# EMS_esp32_wifi_lora_gsm_v2_7_2.net
KiCad netlist of a schematic drawn in EAGLE
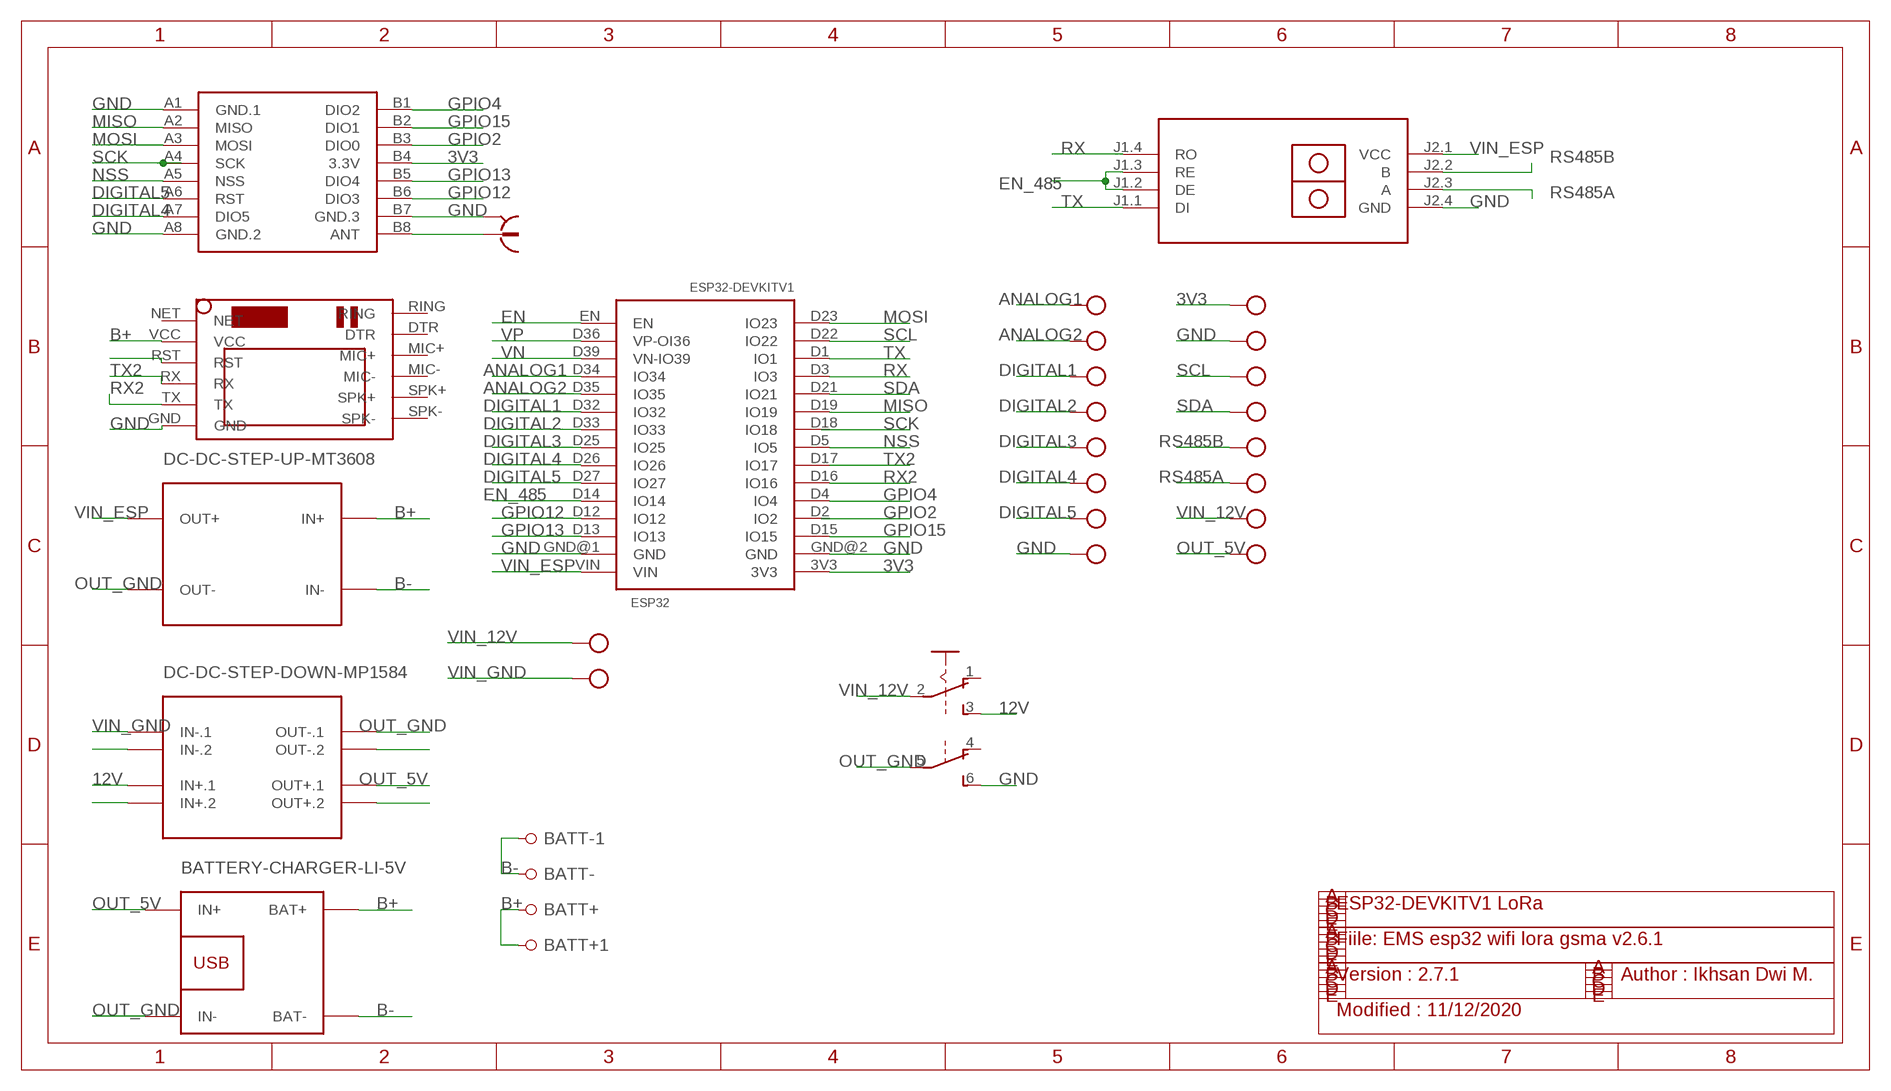
[diagram p0: schematic, sheet 1]

(export (version "E")
  (design (tool "Eeschema 10.0.6"))
  (components
    (comp (ref "3V3__GND")
      (value "MKDSN1,5/2-5,08")
      (footprint "eagle-import:MKDSN1,5_2-5,08")
      (libsource (lib "eagle-import") (part "MKDSN1,5/2-5,08"))
    )
    (comp (ref "12V__5V")
      (value "MKDSN1,5/2-5,08")
      (footprint "eagle-import:MKDSN1,5_2-5,08")
      (libsource (lib "eagle-import") (part "MKDSN1,5/2-5,08"))
    )
    (comp (ref "A1__A2")
      (value "MKDSN1,5/2-5,08")
      (footprint "eagle-import:MKDSN1,5_2-5,08")
      (libsource (lib "eagle-import") (part "MKDSN1,5/2-5,08"))
    )
    (comp (ref "A_____B")
      (value "MKDSN1,5/2-5,08")
      (footprint "eagle-import:MKDSN1,5_2-5,08")
      (libsource (lib "eagle-import") (part "MKDSN1,5/2-5,08"))
    )
    (comp (ref "BATT+")
      (value "PIN-1X1_2.00")
      (footprint "eagle-import:1X01M")
      (libsource (lib "eagle-import") (part "PIN-1X1_2.00"))
    )
    (comp (ref "BATT+1")
      (value "PIN-1X1_2.00")
      (footprint "eagle-import:1X01M")
      (libsource (lib "eagle-import") (part "PIN-1X1_2.00"))
    )
    (comp (ref "BATT-")
      (value "PIN-1X1")
      (footprint "eagle-import:1X01NONAME")
      (libsource (lib "eagle-import") (part "PIN-1X1"))
    )
    (comp (ref "BATT-1")
      (value "PIN-1X1")
      (footprint "eagle-import:1X01NONAME")
      (libsource (lib "eagle-import") (part "PIN-1X1"))
    )
    (comp (ref "D1__D2")
      (value "MKDSN1,5/2-5,08")
      (footprint "eagle-import:MKDSN1,5_2-5,08")
      (libsource (lib "eagle-import") (part "MKDSN1,5/2-5,08"))
    )
    (comp (ref "D3__D4")
      (value "MKDSN1,5/2-5,08")
      (footprint "eagle-import:MKDSN1,5_2-5,08")
      (libsource (lib "eagle-import") (part "MKDSN1,5/2-5,08"))
    )
    (comp (ref "D5_GND")
      (value "MKDSN1,5/2-5,08")
      (footprint "eagle-import:MKDSN1,5_2-5,08")
      (libsource (lib "eagle-import") (part "MKDSN1,5/2-5,08"))
    )
    (comp (ref "ESP32")
      (value "ESP32DEVKITV1")
      (footprint "eagle-import:ESP32-DEVKITV1")
      (libsource (lib "eagle-import") (part "ESP32DEVKITV1"))
    )
    (comp (ref "S1")
      (value "A68-A31")
      (footprint "eagle-import:A68-A31")
      (libsource (lib "eagle-import") (part "A68-A31"))
    )
    (comp (ref "SCL__SDA")
      (value "MKDSN1,5/2-5,08")
      (footprint "eagle-import:MKDSN1,5_2-5,08")
      (libsource (lib "eagle-import") (part "MKDSN1,5/2-5,08"))
    )
    (comp (ref "U$1")
      (value "RS485-TTL-CONVERTER")
      (footprint "eagle-import:RS485-TTL-CONVERTER")
      (libsource (lib "eagle-import") (part "RS485-TTL-CONVERTER"))
    )
    (comp (ref "U$2")
      (value "DC-DC-STEP-UP-MT3608")
      (footprint "eagle-import:DC-DC-STEP-UP-MT3608")
      (libsource (lib "eagle-import") (part "DC-DC-STEP-UP-MT3608"))
    )
    (comp (ref "U$3")
      (value "DC-DC-STEP-DOWN-MP1584")
      (footprint "eagle-import:DC-DC-STEP-DOWN-MP1584")
      (libsource (lib "eagle-import") (part "DC-DC-STEP-DOWN-MP1584"))
    )
    (comp (ref "U$4")
      (value "BATTERY-CHARGER-LI-5V")
      (footprint "eagle-import:BATTERY-CHARGER-LI-5V")
      (libsource (lib "eagle-import") (part "BATTERY-CHARGER-LI-5V"))
    )
    (comp (ref "U$5")
      (value "WIRELESS-LORA-RFM95W#SMD")
      (footprint "eagle-import:WIRELESS-LORA-RFM95W#SMD")
      (libsource (lib "eagle-import") (part "WIRELESS-LORA-RFM95W#SMD"))
    )
    (comp (ref "U$9")
      (value "SIM800LMODULE")
      (footprint "eagle-import:SIM800LMODULE")
      (libsource (lib "eagle-import") (part "SIM800LMODULE"))
    )
    (comp (ref "X1")
      (value "734120110")
      (footprint "eagle-import:734120110")
      (libsource (lib "eagle-import") (part "734120110"))
    )
    (comp (ref "X10")
      (value "MKDSN1,5/2-5,08")
      (footprint "eagle-import:MKDSN1,5_2-5,08")
      (libsource (lib "eagle-import") (part "MKDSN1,5/2-5,08"))
    )
  )
  (nets
    (net (code "1") (name "/3V3") (class "Default")
      (node (ref "3V3__GND") (pin "1") (pinfunction "KL_1") (pintype "passive"))
      (node (ref "ESP32") (pin "3V3") (pinfunction "3V3_3V3") (pintype "bidirectional"))
      (node (ref "U$5") (pin "B4") (pinfunction "3.3V_B4") (pintype "power_in"))
    )
    (net (code "2") (name "/12V") (class "Default")
      (node (ref "S1") (pin "3") (pinfunction "S_3") (pintype "passive"))
      (node (ref "U$3") (pin "IN+.1") (pinfunction "IN+.1_IN+.1") (pintype "bidirectional"))
    )
    (net (code "3") (name "/ANALOG1") (class "Default")
      (node (ref "A1__A2") (pin "1") (pinfunction "KL_1") (pintype "passive"))
      (node (ref "ESP32") (pin "D34") (pinfunction "IO34_D34") (pintype "bidirectional"))
    )
    (net (code "4") (name "/ANALOG2") (class "Default")
      (node (ref "A1__A2") (pin "2") (pinfunction "KL_2") (pintype "passive"))
      (node (ref "ESP32") (pin "D35") (pinfunction "IO35_D35") (pintype "bidirectional"))
    )
    (net (code "5") (name "/B+") (class "Default")
      (node (ref "BATT+") (pin "1") (pinfunction "1_1") (pintype "passive"))
      (node (ref "BATT+1") (pin "1") (pinfunction "1_1") (pintype "passive"))
      (node (ref "U$2") (pin "IN+") (pinfunction "IN+_IN+") (pintype "bidirectional"))
      (node (ref "U$4") (pin "BAT+") (pinfunction "BAT+_BAT+") (pintype "bidirectional"))
      (node (ref "U$9") (pin "VCC") (pinfunction "VCC_VCC") (pintype "bidirectional"))
    )
    (net (code "6") (name "/B-") (class "Default")
      (node (ref "BATT-") (pin "1") (pinfunction "1_1") (pintype "passive"))
      (node (ref "BATT-1") (pin "1") (pinfunction "1_1") (pintype "passive"))
      (node (ref "U$2") (pin "IN-") (pinfunction "IN-_IN-") (pintype "bidirectional"))
      (node (ref "U$4") (pin "BAT-") (pinfunction "BAT-_BAT-") (pintype "bidirectional"))
    )
    (net (code "7") (name "/DIGITAL1") (class "Default")
      (node (ref "D1__D2") (pin "1") (pinfunction "KL_1") (pintype "passive"))
      (node (ref "ESP32") (pin "D32") (pinfunction "IO32_D32") (pintype "bidirectional"))
    )
    (net (code "8") (name "/DIGITAL2") (class "Default")
      (node (ref "D1__D2") (pin "2") (pinfunction "KL_2") (pintype "passive"))
      (node (ref "ESP32") (pin "D33") (pinfunction "IO33_D33") (pintype "bidirectional"))
    )
    (net (code "9") (name "/DIGITAL3") (class "Default")
      (node (ref "D3__D4") (pin "1") (pinfunction "KL_1") (pintype "passive"))
      (node (ref "ESP32") (pin "D25") (pinfunction "IO25_D25") (pintype "bidirectional"))
    )
    (net (code "10") (name "/DIGITAL4") (class "Default")
      (node (ref "D3__D4") (pin "2") (pinfunction "KL_2") (pintype "passive"))
      (node (ref "ESP32") (pin "D26") (pinfunction "IO26_D26") (pintype "bidirectional"))
      (node (ref "U$5") (pin "A7") (pinfunction "DIO5_A7") (pintype "bidirectional"))
    )
    (net (code "11") (name "/DIGITAL5") (class "Default")
      (node (ref "D5_GND") (pin "1") (pinfunction "KL_1") (pintype "passive"))
      (node (ref "ESP32") (pin "D27") (pinfunction "IO27_D27") (pintype "bidirectional"))
      (node (ref "U$5") (pin "A6") (pinfunction "RST_A6") (pintype "bidirectional"))
    )
    (net (code "12") (name "/EN") (class "Default")
      (node (ref "ESP32") (pin "EN") (pinfunction "EN_EN") (pintype "bidirectional"))
    )
    (net (code "13") (name "/EN_485") (class "Default")
      (node (ref "ESP32") (pin "D14") (pinfunction "IO14_D14") (pintype "bidirectional"))
      (node (ref "U$1") (pin "J1.2") (pinfunction "DE_J1.2") (pintype "passive"))
      (node (ref "U$1") (pin "J1.3") (pinfunction "RE_J1.3") (pintype "passive"))
    )
    (net (code "14") (name "/GND") (class "Default")
      (node (ref "3V3__GND") (pin "2") (pinfunction "KL_2") (pintype "passive"))
      (node (ref "D5_GND") (pin "2") (pinfunction "KL_2") (pintype "passive"))
      (node (ref "ESP32") (pin "GND@1") (pinfunction "GND_GND@1") (pintype "bidirectional"))
      (node (ref "ESP32") (pin "GND@2") (pinfunction "GND_GND@2") (pintype "bidirectional"))
      (node (ref "S1") (pin "6") (pinfunction "S_6") (pintype "passive"))
      (node (ref "U$1") (pin "J2.4") (pinfunction "GND_J2.4") (pintype "power_in"))
      (node (ref "U$5") (pin "A1") (pinfunction "GND.1_A1") (pintype "power_in"))
      (node (ref "U$5") (pin "A8") (pinfunction "GND.2_A8") (pintype "power_in"))
      (node (ref "U$5") (pin "B7") (pinfunction "GND.3_B7") (pintype "power_in"))
      (node (ref "U$9") (pin "GND") (pinfunction "GND_GND") (pintype "bidirectional"))
      (node (ref "X1") (pin "S@1") (pinfunction "2_S@1") (pintype "passive"))
      (node (ref "X1") (pin "S@2") (pinfunction "2_S@2") (pintype "passive"))
      (node (ref "X1") (pin "S@3") (pinfunction "2_S@3") (pintype "passive"))
    )
    (net (code "15") (name "/GPIO2") (class "Default")
      (node (ref "ESP32") (pin "D2") (pinfunction "IO2_D2") (pintype "bidirectional"))
      (node (ref "U$5") (pin "B3") (pinfunction "DIO0_B3") (pintype "bidirectional"))
    )
    (net (code "16") (name "/GPIO4") (class "Default")
      (node (ref "ESP32") (pin "D4") (pinfunction "IO4_D4") (pintype "bidirectional"))
      (node (ref "U$5") (pin "B1") (pinfunction "DIO2_B1") (pintype "bidirectional"))
    )
    (net (code "17") (name "/GPIO12") (class "Default")
      (node (ref "ESP32") (pin "D12") (pinfunction "IO12_D12") (pintype "bidirectional"))
      (node (ref "U$5") (pin "B6") (pinfunction "DIO3_B6") (pintype "bidirectional"))
    )
    (net (code "18") (name "/GPIO13") (class "Default")
      (node (ref "ESP32") (pin "D13") (pinfunction "IO13_D13") (pintype "bidirectional"))
      (node (ref "U$5") (pin "B5") (pinfunction "DIO4_B5") (pintype "bidirectional"))
    )
    (net (code "19") (name "/GPIO15") (class "Default")
      (node (ref "ESP32") (pin "D15") (pinfunction "IO15_D15") (pintype "bidirectional"))
      (node (ref "U$5") (pin "B2") (pinfunction "DIO1_B2") (pintype "bidirectional"))
    )
    (net (code "20") (name "/MISO") (class "Default")
      (node (ref "ESP32") (pin "D19") (pinfunction "IO19_D19") (pintype "bidirectional"))
      (node (ref "U$5") (pin "A2") (pinfunction "MISO_A2") (pintype "bidirectional"))
    )
    (net (code "21") (name "/MOSI") (class "Default")
      (node (ref "ESP32") (pin "D23") (pinfunction "IO23_D23") (pintype "bidirectional"))
      (node (ref "U$5") (pin "A3") (pinfunction "MOSI_A3") (pintype "bidirectional"))
    )
    (net (code "22") (name "/NSS") (class "Default")
      (node (ref "ESP32") (pin "D5") (pinfunction "IO5_D5") (pintype "bidirectional"))
      (node (ref "U$5") (pin "A5") (pinfunction "NSS_A5") (pintype "bidirectional"))
    )
    (net (code "23") (name "/OUT_5V") (class "Default")
      (node (ref "12V__5V") (pin "2") (pinfunction "KL_2") (pintype "passive"))
      (node (ref "U$3") (pin "OUT+.1") (pinfunction "OUT+.1_OUT+.1") (pintype "bidirectional"))
      (node (ref "U$4") (pin "IN+") (pinfunction "IN+_IN+") (pintype "bidirectional"))
    )
    (net (code "24") (name "/OUT_GND") (class "Default")
      (node (ref "S1") (pin "5") (pinfunction "P_5") (pintype "passive"))
      (node (ref "U$2") (pin "OUT-") (pinfunction "OUT-_OUT-") (pintype "bidirectional"))
      (node (ref "U$3") (pin "OUT-.1") (pinfunction "OUT-.1_OUT-.1") (pintype "bidirectional"))
      (node (ref "U$4") (pin "IN-") (pinfunction "IN-_IN-") (pintype "bidirectional"))
    )
    (net (code "25") (name "/RS485A") (class "Default")
      (node (ref "A_____B") (pin "2") (pinfunction "KL_2") (pintype "passive"))
      (node (ref "U$1") (pin "J2.3") (pinfunction "A_J2.3") (pintype "passive"))
    )
    (net (code "26") (name "/RS485B") (class "Default")
      (node (ref "A_____B") (pin "1") (pinfunction "KL_1") (pintype "passive"))
      (node (ref "U$1") (pin "J2.2") (pinfunction "B_J2.2") (pintype "passive"))
    )
    (net (code "27") (name "/RX") (class "Default")
      (node (ref "ESP32") (pin "D3") (pinfunction "IO3_D3") (pintype "bidirectional"))
      (node (ref "U$1") (pin "J1.4") (pinfunction "RO_J1.4") (pintype "passive"))
    )
    (net (code "28") (name "/RX2") (class "Default")
      (node (ref "ESP32") (pin "D16") (pinfunction "IO16_D16") (pintype "bidirectional"))
      (node (ref "U$9") (pin "TX") (pinfunction "TX_TX") (pintype "bidirectional"))
    )
    (net (code "29") (name "/SCK") (class "Default")
      (node (ref "ESP32") (pin "D18") (pinfunction "IO18_D18") (pintype "bidirectional"))
      (node (ref "U$5") (pin "A4") (pinfunction "SCK_A4") (pintype "bidirectional"))
    )
    (net (code "30") (name "/SCL") (class "Default")
      (node (ref "ESP32") (pin "D22") (pinfunction "IO22_D22") (pintype "bidirectional"))
      (node (ref "SCL__SDA") (pin "1") (pinfunction "KL_1") (pintype "passive"))
    )
    (net (code "31") (name "/SDA") (class "Default")
      (node (ref "ESP32") (pin "D21") (pinfunction "IO21_D21") (pintype "bidirectional"))
      (node (ref "SCL__SDA") (pin "2") (pinfunction "KL_2") (pintype "passive"))
    )
    (net (code "32") (name "/TX") (class "Default")
      (node (ref "ESP32") (pin "D1") (pinfunction "IO1_D1") (pintype "bidirectional"))
      (node (ref "U$1") (pin "J1.1") (pinfunction "DI_J1.1") (pintype "passive"))
    )
    (net (code "33") (name "/TX2") (class "Default")
      (node (ref "ESP32") (pin "D17") (pinfunction "IO17_D17") (pintype "bidirectional"))
      (node (ref "U$9") (pin "RX") (pinfunction "RX_RX") (pintype "bidirectional"))
    )
    (net (code "34") (name "/VIN_12V") (class "Default")
      (node (ref "12V__5V") (pin "1") (pinfunction "KL_1") (pintype "passive"))
      (node (ref "S1") (pin "2") (pinfunction "P_2") (pintype "passive"))
      (node (ref "X10") (pin "1") (pinfunction "KL_1") (pintype "passive"))
    )
    (net (code "35") (name "/VIN_ESP") (class "Default")
      (node (ref "ESP32") (pin "VIN") (pinfunction "VIN_VIN") (pintype "bidirectional"))
      (node (ref "U$1") (pin "J2.1") (pinfunction "VCC_J2.1") (pintype "power_in"))
      (node (ref "U$2") (pin "OUT+") (pinfunction "OUT+_OUT+") (pintype "bidirectional"))
    )
    (net (code "36") (name "/VIN_GND") (class "Default")
      (node (ref "U$3") (pin "IN-.1") (pinfunction "IN-.1_IN-.1") (pintype "bidirectional"))
      (node (ref "X10") (pin "2") (pinfunction "KL_2") (pintype "passive"))
    )
    (net (code "37") (name "/VN") (class "Default")
      (node (ref "ESP32") (pin "D39") (pinfunction "VN-IO39_D39") (pintype "bidirectional"))
    )
    (net (code "38") (name "/VP") (class "Default")
      (node (ref "ESP32") (pin "D36") (pinfunction "VP-OI36_D36") (pintype "bidirectional"))
    )
    (net (code "39") (name "Net-(U$5-ANT)") (class "Default")
      (node (ref "U$5") (pin "B8") (pinfunction "ANT_B8") (pintype "passive"))
      (node (ref "X1") (pin "1") (pinfunction "1_1") (pintype "passive"))
    )
    (net (code "40") (name "unconnected-(S1A-O-Pad1)") (class "Default")
      (node (ref "S1") (pin "1") (pinfunction "O_1") (pintype "passive"))
    )
    (net (code "41") (name "unconnected-(S1B-O-Pad4)") (class "Default")
      (node (ref "S1") (pin "4") (pinfunction "O_4") (pintype "passive"))
    )
    (net (code "42") (name "unconnected-(U$3-PadIN+.2)") (class "Default")
      (node (ref "U$3") (pin "IN+.2") (pinfunction "IN+.2_IN+.2") (pintype "bidirectional"))
    )
    (net (code "43") (name "unconnected-(U$3-PadIN-.2)") (class "Default")
      (node (ref "U$3") (pin "IN-.2") (pinfunction "IN-.2_IN-.2") (pintype "bidirectional"))
    )
    (net (code "44") (name "unconnected-(U$3-PadOUT+.2)") (class "Default")
      (node (ref "U$3") (pin "OUT+.2") (pinfunction "OUT+.2_OUT+.2") (pintype "bidirectional"))
    )
    (net (code "45") (name "unconnected-(U$3-PadOUT-.2)") (class "Default")
      (node (ref "U$3") (pin "OUT-.2") (pinfunction "OUT-.2_OUT-.2") (pintype "bidirectional"))
    )
    (net (code "46") (name "unconnected-(U$9-PadDTR)") (class "Default")
      (node (ref "U$9") (pin "DTR") (pinfunction "DTR_DTR") (pintype "bidirectional"))
    )
    (net (code "47") (name "unconnected-(U$9-PadMIC+)") (class "Default")
      (node (ref "U$9") (pin "MIC+") (pinfunction "MIC+_MIC+") (pintype "bidirectional"))
    )
    (net (code "48") (name "unconnected-(U$9-PadMIC-)") (class "Default")
      (node (ref "U$9") (pin "MIC-") (pinfunction "MIC-_MIC-") (pintype "bidirectional"))
    )
    (net (code "49") (name "unconnected-(U$9-PadNET)") (class "Default")
      (node (ref "U$9") (pin "NET") (pinfunction "NET_NET") (pintype "bidirectional"))
    )
    (net (code "50") (name "unconnected-(U$9-PadRING)") (class "Default")
      (node (ref "U$9") (pin "RING") (pinfunction "RING_RING") (pintype "bidirectional"))
    )
    (net (code "51") (name "unconnected-(U$9-PadRST)") (class "Default")
      (node (ref "U$9") (pin "RST") (pinfunction "RST_RST") (pintype "bidirectional"))
    )
    (net (code "52") (name "unconnected-(U$9-PadSPK+)") (class "Default")
      (node (ref "U$9") (pin "SPK+") (pinfunction "SPK+_SPK+") (pintype "bidirectional"))
    )
    (net (code "53") (name "unconnected-(U$9-PadSPK-)") (class "Default")
      (node (ref "U$9") (pin "SPK-") (pinfunction "SPK-_SPK-") (pintype "bidirectional"))
    )
  )
)
